# HelloWorldSMD.net
KiCad netlist of a schematic drawn in EAGLE
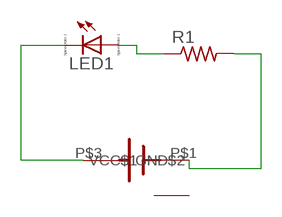
[diagram p0: schematic, sheet 1]

(export (version "E")
  (design (tool "Eeschema 10.0.6"))
  (components
    (comp (ref "LED1")
      (value "LED_E")
      (footprint "eagle-import:LED_1206")
      (libsource (lib "eagle-import") (part "LED_E"))
    )
    (comp (ref "R1")
      (value "R-US_R0805")
      (footprint "eagle-import:R0805")
      (libsource (lib "eagle-import") (part "R-US_R0805"))
    )
    (comp (ref "U$1")
      (value "CR1025")
      (footprint "eagle-import:CR1025")
      (libsource (lib "eagle-import") (part "CR1025"))
    )
  )
  (nets
    (net (code "1") (name "/VCC") (class "Default")
      (node (ref "U$1") (pin "P$2") (pinfunction "VCC_P$2") (pintype "power_in"))
    )
    (net (code "2") (name "Net-(LED1-PadA)") (class "Default")
      (node (ref "LED1") (pin "A") (pinfunction "A_A") (pintype "passive"))
      (node (ref "R1") (pin "1") (pinfunction "1_1") (pintype "passive"))
    )
    (net (code "3") (name "Net-(U$1-GND$2)") (class "Default")
      (node (ref "LED1") (pin "C") (pinfunction "C_C") (pintype "passive"))
      (node (ref "U$1") (pin "P$3") (pinfunction "GND$2_P$3") (pintype "power_in"))
    )
    (net (code "4") (name "Net-(U$1-VCC$1)") (class "Default")
      (node (ref "R1") (pin "2") (pinfunction "2_2") (pintype "passive"))
      (node (ref "U$1") (pin "P$1") (pinfunction "VCC$1_P$1") (pintype "power_in"))
    )
  )
)
